# Headphone-Amplifier-ClassAB-alt.net
KiCad netlist of a schematic drawn in EAGLE
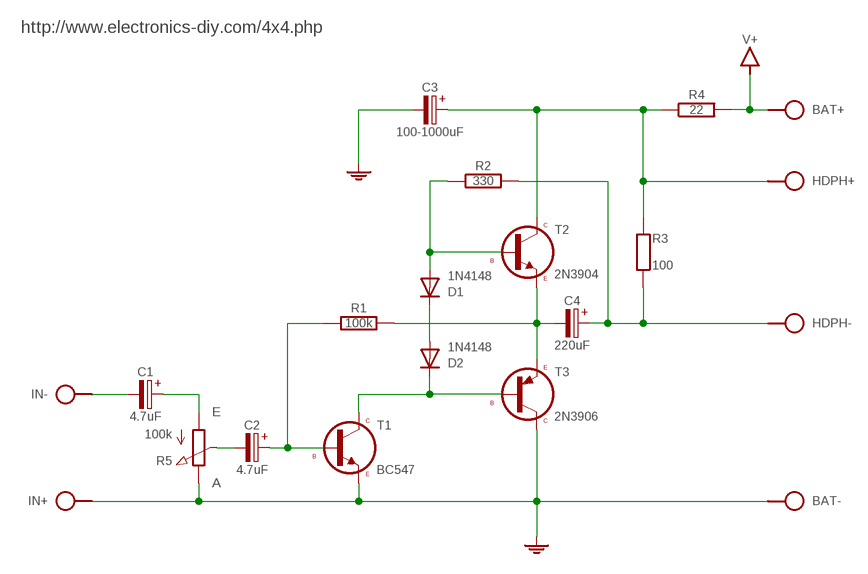
[diagram p0: schematic, sheet 1]

(export (version "E")
  (design (tool "Eeschema 10.0.6"))
  (components
    (comp (ref "BAT")
      (value "SPAD+-+-")
      (footprint "eagle-import:SPAD+-")
      (libsource (lib "eagle-import") (part "SPAD+-+-"))
    )
    (comp (ref "C1")
      (value "4.7uF")
      (footprint "eagle-import:E2,5-3")
      (libsource (lib "eagle-import") (part "CPOLE2,5-3"))
    )
    (comp (ref "C2")
      (value "4.7uF")
      (footprint "eagle-import:E2,5-3")
      (libsource (lib "eagle-import") (part "CPOLE2,5-3"))
    )
    (comp (ref "C3")
      (value "100-1000uF")
      (footprint "eagle-import:E2.5-4_V")
      (libsource (lib "eagle-import") (part "CPOLE2,5-4/V"))
    )
    (comp (ref "C4")
      (value "220uF")
      (footprint "eagle-import:E5-4")
      (libsource (lib "eagle-import") (part "CPOLE5-4"))
    )
    (comp (ref "D1")
      (value "1N4148")
      (footprint "eagle-import:DO34-5-V")
      (libsource (lib "eagle-import") (part "DIODE34-5-V"))
    )
    (comp (ref "D2")
      (value "1N4148")
      (footprint "eagle-import:DO34-5V")
      (libsource (lib "eagle-import") (part "DIODE34-5V"))
    )
    (comp (ref "HDPH")
      (value "SPAD+--+")
      (footprint "eagle-import:SPAD-+")
      (libsource (lib "eagle-import") (part "SPAD+--+"))
    )
    (comp (ref "IN")
      (value "SPAD+-+-")
      (footprint "eagle-import:SPAD+-")
      (libsource (lib "eagle-import") (part "SPAD+-+-"))
    )
    (comp (ref "R1")
      (value "100k")
      (footprint "eagle-import:0204_10")
      (libsource (lib "eagle-import") (part "R-H0204/10"))
    )
    (comp (ref "R2")
      (value "330")
      (footprint "eagle-import:0204_10")
      (libsource (lib "eagle-import") (part "R-H0204/10"))
    )
    (comp (ref "R3")
      (value "100")
      (footprint "eagle-import:0204_10")
      (libsource (lib "eagle-import") (part "R0204/10"))
    )
    (comp (ref "R4")
      (value "22")
      (footprint "eagle-import:0204_10")
      (libsource (lib "eagle-import") (part "R-H0204/10"))
    )
    (comp (ref "R5")
      (value "100k")
      (footprint "eagle-import:CONN-3P")
      (libsource (lib "eagle-import") (part "POT-3P"))
    )
    (comp (ref "T1")
      (value "BC547")
      (footprint "eagle-import:TO92")
      (libsource (lib "eagle-import") (part "2N3904"))
    )
    (comp (ref "T2")
      (value "2N3904")
      (footprint "eagle-import:TO92")
      (libsource (lib "eagle-import") (part "2N3904"))
    )
    (comp (ref "T3")
      (value "2N3906")
      (footprint "eagle-import:TO92")
      (libsource (lib "eagle-import") (part "2N3906"))
    )
  )
  (nets
    (net (code "1") (name "GND") (class "Default")
      (node (ref "BAT") (pin "1") (pinfunction "P$1_1") (pintype "passive"))
      (node (ref "C3") (pin "-") (pinfunction "-_-") (pintype "passive"))
      (node (ref "IN") (pin "2") (pinfunction "P$1_2") (pintype "passive"))
      (node (ref "R5") (pin "3") (pinfunction "E_3") (pintype "passive"))
      (node (ref "T1") (pin "1") (pinfunction "E_1") (pintype "passive"))
      (node (ref "T3") (pin "3") (pinfunction "C_3") (pintype "passive"))
    )
    (net (code "2") (name "Net-(D1-PadC)") (class "Default")
      (node (ref "D1") (pin "C") (pinfunction "C_C") (pintype "passive"))
      (node (ref "D2") (pin "A") (pinfunction "A_A") (pintype "passive"))
    )
    (net (code "3") (name "Net-(HDPHA-P$1)") (class "Default")
      (node (ref "C3") (pin "+") (pinfunction "+_+") (pintype "passive"))
      (node (ref "HDPH") (pin "2") (pinfunction "P$1_2") (pintype "passive"))
      (node (ref "R3") (pin "1") (pinfunction "2_1") (pintype "passive"))
      (node (ref "R4") (pin "1") (pinfunction "1_1") (pintype "passive"))
      (node (ref "T2") (pin "3") (pinfunction "C_3") (pintype "passive"))
    )
    (net (code "4") (name "Net-(HDPHB-P$1)") (class "Default")
      (node (ref "C4") (pin "+") (pinfunction "+_+") (pintype "passive"))
      (node (ref "HDPH") (pin "1") (pinfunction "P$1_1") (pintype "passive"))
      (node (ref "R2") (pin "2") (pinfunction "2_2") (pintype "passive"))
      (node (ref "R3") (pin "2") (pinfunction "1_2") (pintype "passive"))
    )
    (net (code "5") (name "Net-(INB-P$1)") (class "Default")
      (node (ref "C1") (pin "-") (pinfunction "-_-") (pintype "passive"))
      (node (ref "IN") (pin "1") (pinfunction "P$1_1") (pintype "passive"))
    )
    (net (code "6") (name "Net-(R5-A)") (class "Default")
      (node (ref "C1") (pin "+") (pinfunction "+_+") (pintype "passive"))
      (node (ref "R5") (pin "1") (pinfunction "A_1") (pintype "passive"))
    )
    (net (code "7") (name "Net-(R5-S)") (class "Default")
      (node (ref "C2") (pin "-") (pinfunction "-_-") (pintype "passive"))
      (node (ref "R5") (pin "2") (pinfunction "S_2") (pintype "passive"))
    )
    (net (code "8") (name "Net-(T1-B)") (class "Default")
      (node (ref "C2") (pin "+") (pinfunction "+_+") (pintype "passive"))
      (node (ref "R1") (pin "1") (pinfunction "1_1") (pintype "passive"))
      (node (ref "T1") (pin "2") (pinfunction "B_2") (pintype "passive"))
    )
    (net (code "9") (name "Net-(T1-C)") (class "Default")
      (node (ref "D2") (pin "C") (pinfunction "C_C") (pintype "passive"))
      (node (ref "T1") (pin "3") (pinfunction "C_3") (pintype "passive"))
      (node (ref "T3") (pin "2") (pinfunction "B_2") (pintype "passive"))
    )
    (net (code "10") (name "Net-(T2-B)") (class "Default")
      (node (ref "D1") (pin "A") (pinfunction "A_A") (pintype "passive"))
      (node (ref "R2") (pin "1") (pinfunction "1_1") (pintype "passive"))
      (node (ref "T2") (pin "2") (pinfunction "B_2") (pintype "passive"))
    )
    (net (code "11") (name "Net-(T2-E)") (class "Default")
      (node (ref "C4") (pin "-") (pinfunction "-_-") (pintype "passive"))
      (node (ref "R1") (pin "2") (pinfunction "2_2") (pintype "passive"))
      (node (ref "T2") (pin "1") (pinfunction "E_1") (pintype "passive"))
      (node (ref "T3") (pin "1") (pinfunction "E_1") (pintype "passive"))
    )
    (net (code "12") (name "V+") (class "Default")
      (node (ref "BAT") (pin "2") (pinfunction "P$1_2") (pintype "passive"))
      (node (ref "R4") (pin "2") (pinfunction "2_2") (pintype "passive"))
    )
  )
)
